# LEDDriverBoardV1_2.net
KiCad netlist of a schematic drawn in EAGLE
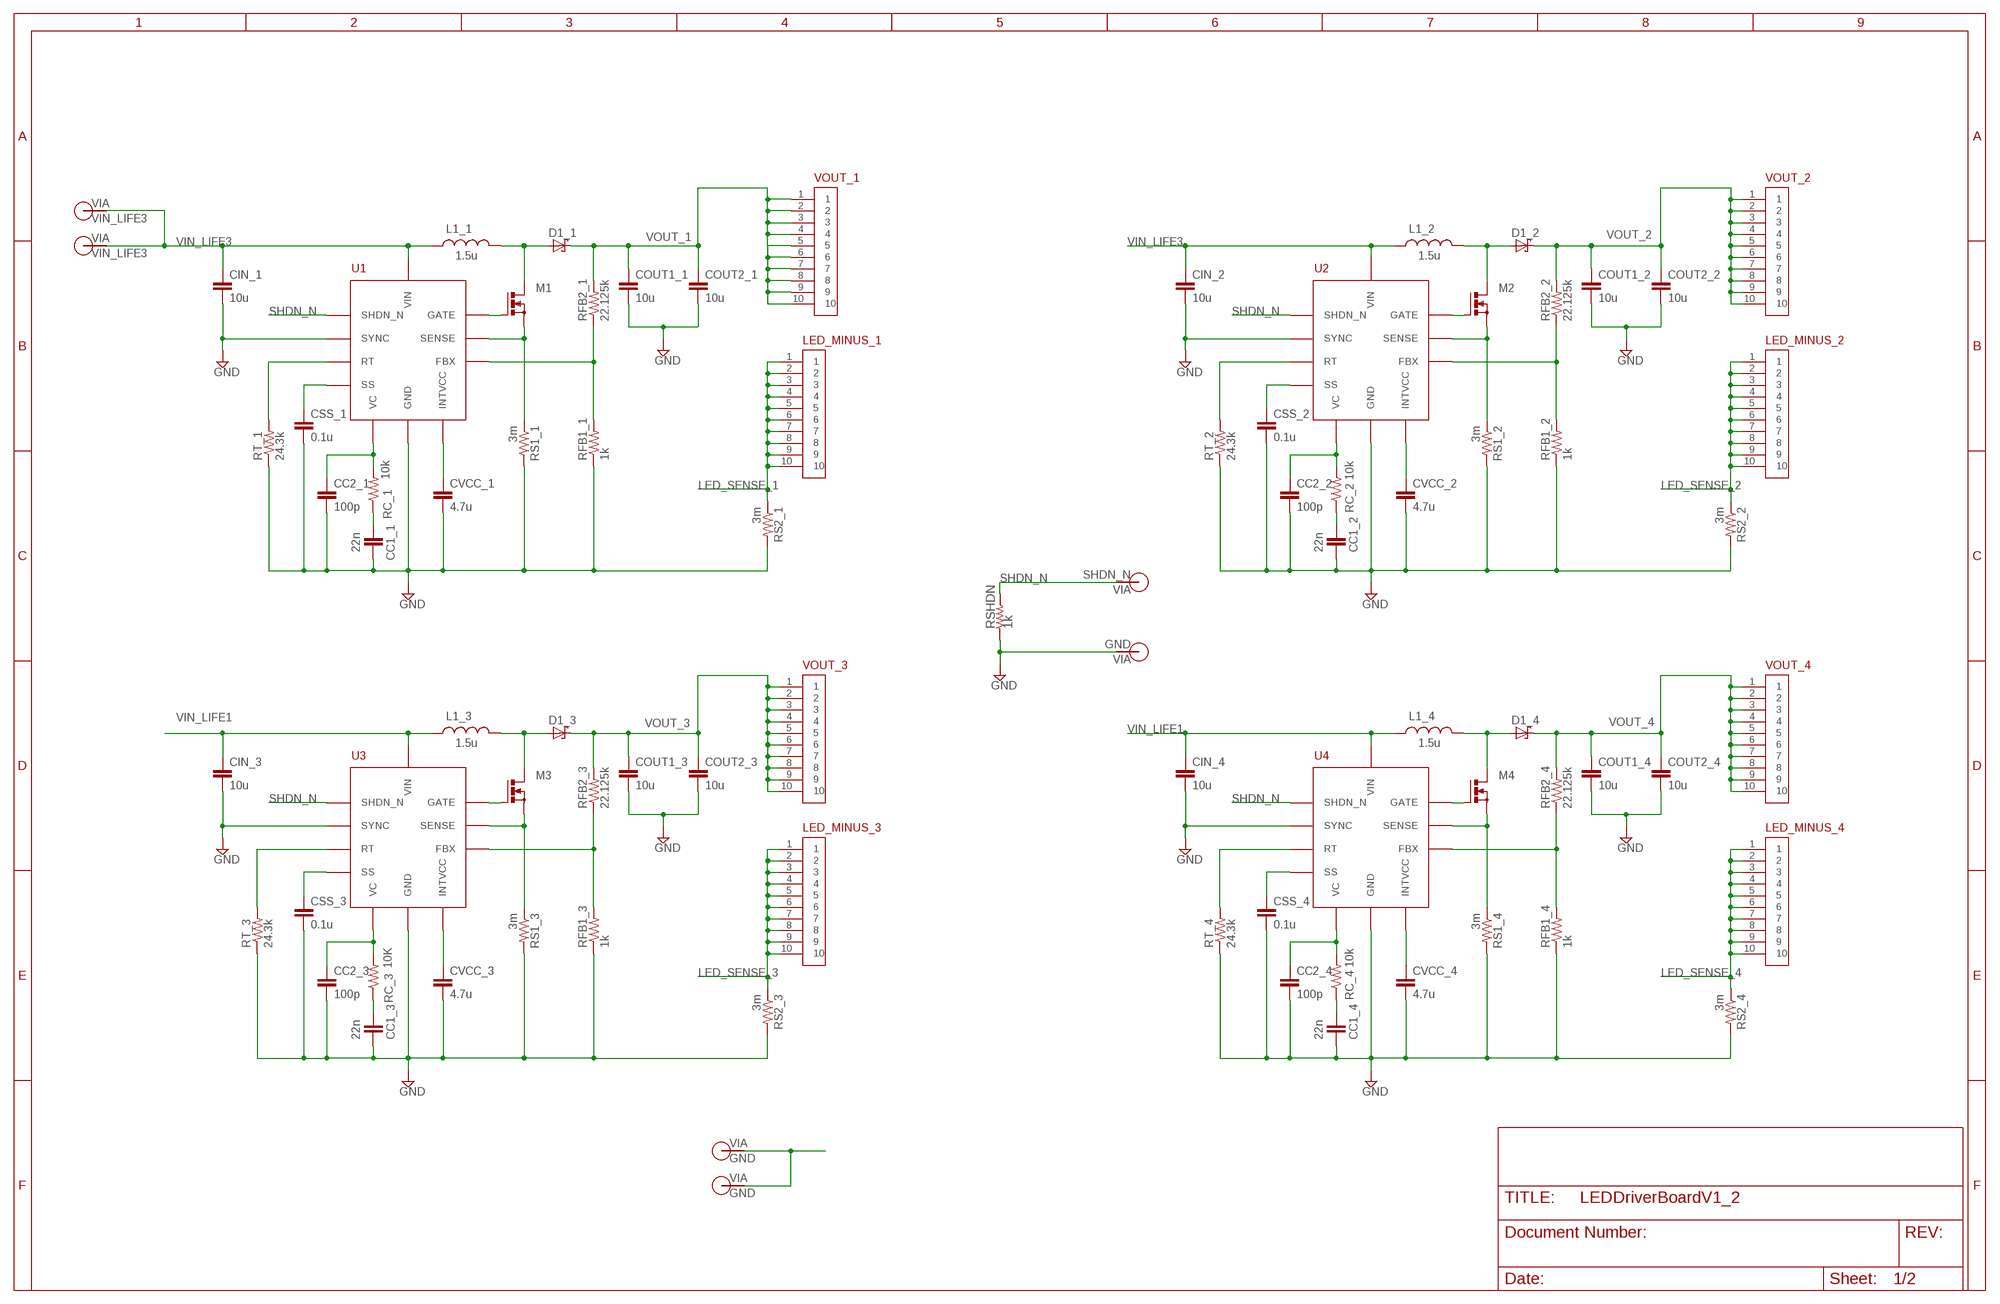
[diagram p0: schematic, sheet 1]
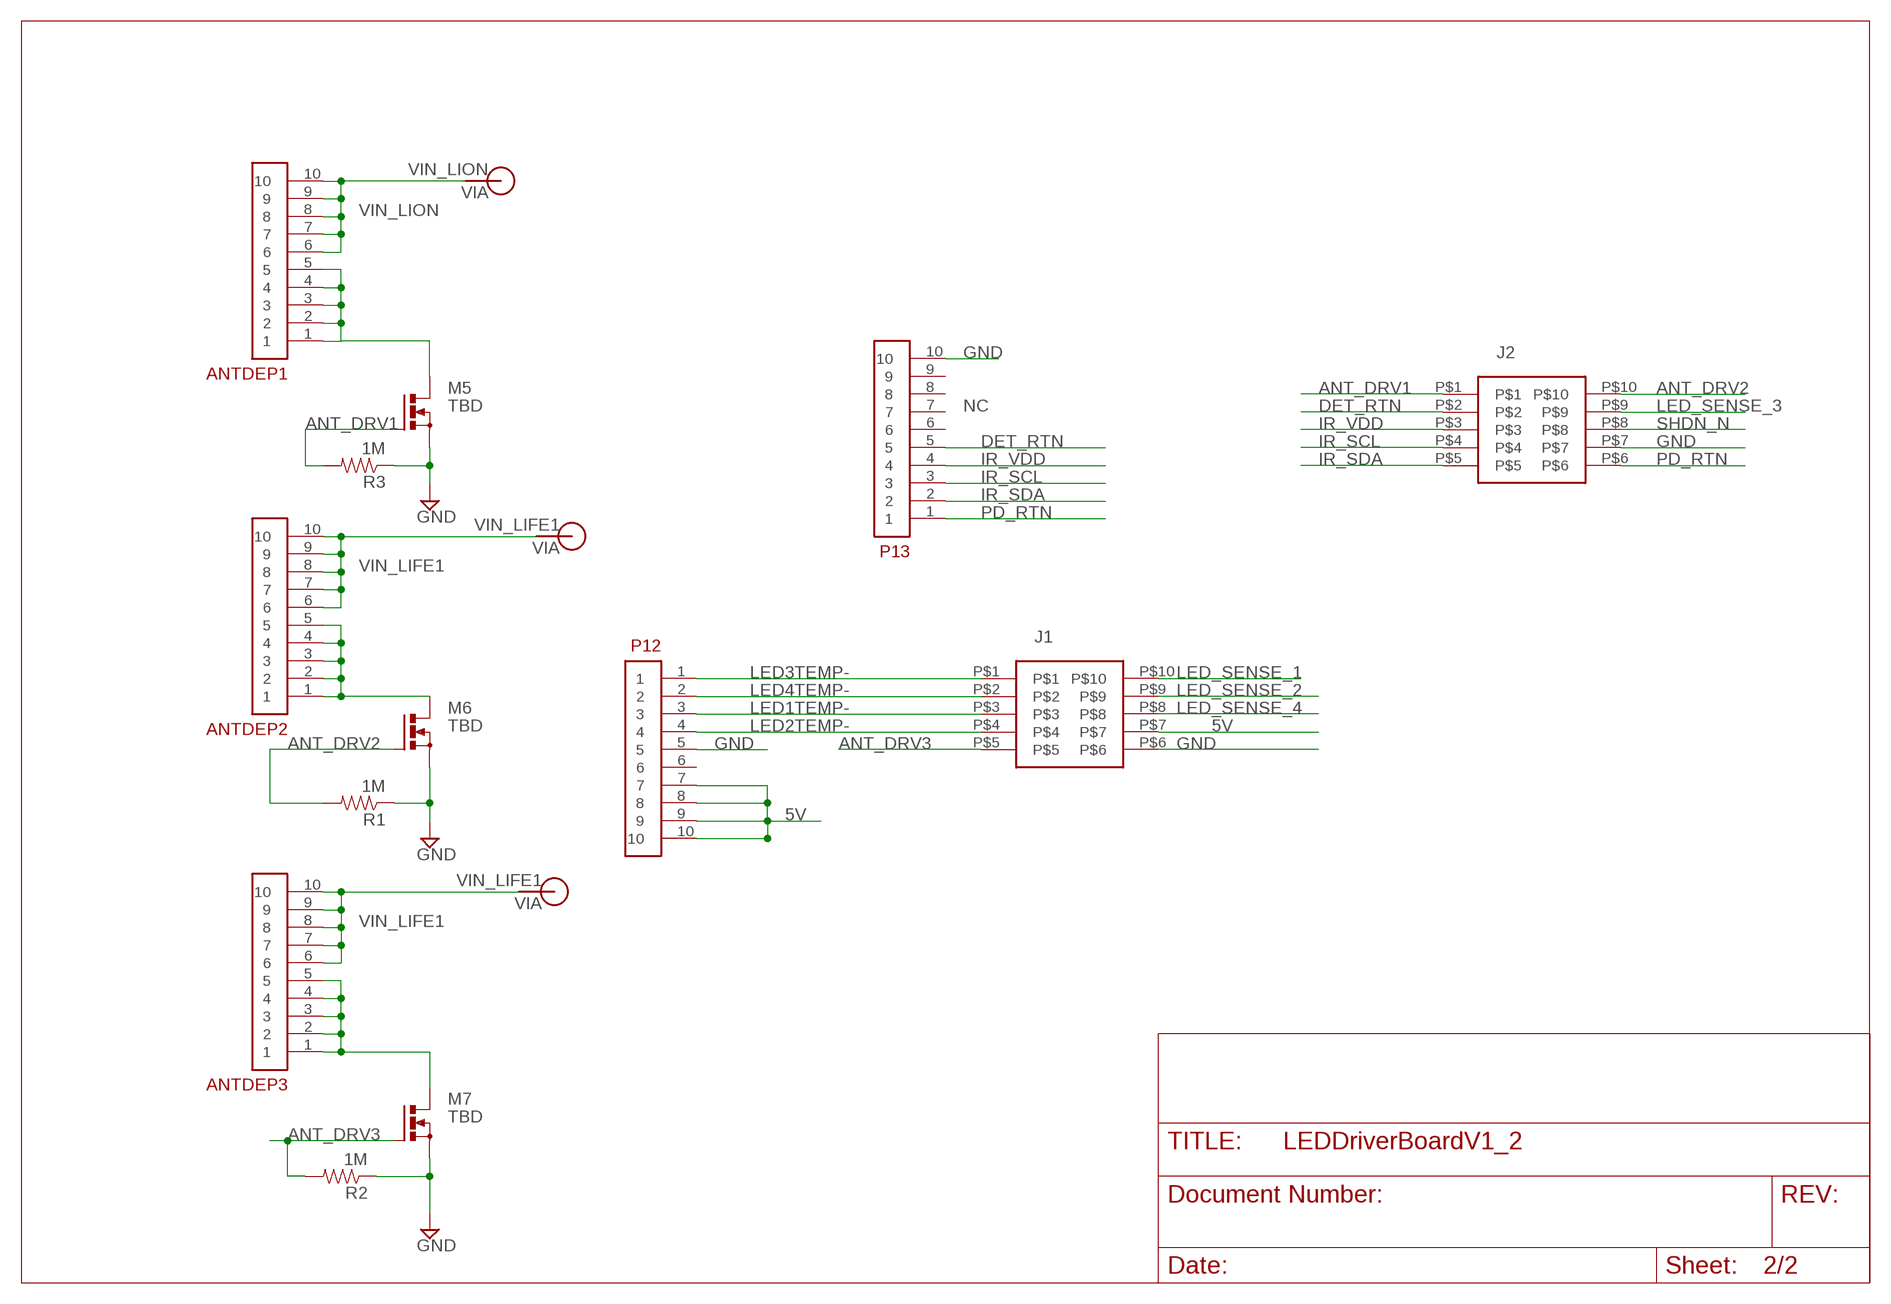
[diagram p1: schematic, sheet 2]

(export (version "E")
  (design (tool "Eeschema 10.0.6"))
  (components
    (comp (ref "CC1_1")
      (value "22n")
      (footprint "eagle-import:C0603")
      (libsource (lib "eagle-import") (part "C-EUC0603"))
    )
    (comp (ref "CC1_2")
      (value "22n")
      (footprint "eagle-import:C0603")
      (libsource (lib "eagle-import") (part "C-EUC0603"))
    )
    (comp (ref "CC1_3")
      (value "22n")
      (footprint "eagle-import:C0603")
      (libsource (lib "eagle-import") (part "C-EUC0603"))
    )
    (comp (ref "CC1_4")
      (value "22n")
      (footprint "eagle-import:C0603")
      (libsource (lib "eagle-import") (part "C-EUC0603"))
    )
    (comp (ref "CC2_1")
      (value "100p")
      (footprint "eagle-import:C0603")
      (libsource (lib "eagle-import") (part "C-EUC0603"))
    )
    (comp (ref "CC2_2")
      (value "100p")
      (footprint "eagle-import:C0603")
      (libsource (lib "eagle-import") (part "C-EUC0603"))
    )
    (comp (ref "CC2_3")
      (value "100p")
      (footprint "eagle-import:C0603")
      (libsource (lib "eagle-import") (part "C-EUC0603"))
    )
    (comp (ref "CC2_4")
      (value "100p")
      (footprint "eagle-import:C0603")
      (libsource (lib "eagle-import") (part "C-EUC0603"))
    )
    (comp (ref "CIN_1")
      (value "10u")
      (footprint "eagle-import:C1210")
      (libsource (lib "eagle-import") (part "C-EUC1210"))
    )
    (comp (ref "CIN_2")
      (value "10u")
      (footprint "eagle-import:C1210")
      (libsource (lib "eagle-import") (part "C-EUC1210"))
    )
    (comp (ref "CIN_3")
      (value "10u")
      (footprint "eagle-import:C1210")
      (libsource (lib "eagle-import") (part "C-EUC1210"))
    )
    (comp (ref "CIN_4")
      (value "10u")
      (footprint "eagle-import:C1210")
      (libsource (lib "eagle-import") (part "C-EUC1210"))
    )
    (comp (ref "COUT1_1")
      (value "10u")
      (footprint "eagle-import:C1210")
      (libsource (lib "eagle-import") (part "C-EUC1210"))
    )
    (comp (ref "COUT1_2")
      (value "10u")
      (footprint "eagle-import:C1210")
      (libsource (lib "eagle-import") (part "C-EUC1210"))
    )
    (comp (ref "COUT1_3")
      (value "10u")
      (footprint "eagle-import:C1210")
      (libsource (lib "eagle-import") (part "C-EUC1210"))
    )
    (comp (ref "COUT1_4")
      (value "10u")
      (footprint "eagle-import:C1210")
      (libsource (lib "eagle-import") (part "C-EUC1210"))
    )
    (comp (ref "COUT2_1")
      (value "10u")
      (footprint "eagle-import:C1210")
      (libsource (lib "eagle-import") (part "C-EUC1210"))
    )
    (comp (ref "COUT2_2")
      (value "10u")
      (footprint "eagle-import:C1210")
      (libsource (lib "eagle-import") (part "C-EUC1210"))
    )
    (comp (ref "COUT2_3")
      (value "10u")
      (footprint "eagle-import:C1210")
      (libsource (lib "eagle-import") (part "C-EUC1210"))
    )
    (comp (ref "COUT2_4")
      (value "10u")
      (footprint "eagle-import:C1210")
      (libsource (lib "eagle-import") (part "C-EUC1210"))
    )
    (comp (ref "CSS_1")
      (value "0.1u")
      (footprint "eagle-import:C0603")
      (libsource (lib "eagle-import") (part "C-EUC0603"))
    )
    (comp (ref "CSS_2")
      (value "0.1u")
      (footprint "eagle-import:C0603")
      (libsource (lib "eagle-import") (part "C-EUC0603"))
    )
    (comp (ref "CSS_3")
      (value "0.1u")
      (footprint "eagle-import:C0603")
      (libsource (lib "eagle-import") (part "C-EUC0603"))
    )
    (comp (ref "CSS_4")
      (value "0.1u")
      (footprint "eagle-import:C0603")
      (libsource (lib "eagle-import") (part "C-EUC0603"))
    )
    (comp (ref "CVCC_1")
      (value "4.7u")
      (footprint "eagle-import:C0603")
      (libsource (lib "eagle-import") (part "C-EUC0603"))
    )
    (comp (ref "CVCC_2")
      (value "4.7u")
      (footprint "eagle-import:C0603")
      (libsource (lib "eagle-import") (part "C-EUC0603"))
    )
    (comp (ref "CVCC_3")
      (value "4.7u")
      (footprint "eagle-import:C0603")
      (libsource (lib "eagle-import") (part "C-EUC0603"))
    )
    (comp (ref "CVCC_4")
      (value "4.7u")
      (footprint "eagle-import:C0603")
      (libsource (lib "eagle-import") (part "C-EUC0603"))
    )
    (comp (ref "D1_1")
      (value "CDBZ5T30100-HF")
      (footprint "eagle-import:SMC(Z5-T)")
      (libsource (lib "eagle-import") (part "CDBZ5T30100-HF"))
    )
    (comp (ref "D1_2")
      (value "CDBZ5T30100-HF")
      (footprint "eagle-import:SMC(Z5-T)")
      (libsource (lib "eagle-import") (part "CDBZ5T30100-HF"))
    )
    (comp (ref "D1_3")
      (value "CDBZ5T30100-HF")
      (footprint "eagle-import:SMC(Z5-T)")
      (libsource (lib "eagle-import") (part "CDBZ5T30100-HF"))
    )
    (comp (ref "D1_4")
      (value "CDBZ5T30100-HF")
      (footprint "eagle-import:SMC(Z5-T)")
      (libsource (lib "eagle-import") (part "CDBZ5T30100-HF"))
    )
    (comp (ref "L1_1")
      (value "1.5u")
      (footprint "eagle-import:SRP1245A")
      (libsource (lib "eagle-import") (part "SRP1245A-1R5M"))
    )
    (comp (ref "L1_2")
      (value "1.5u")
      (footprint "eagle-import:SRP1245A")
      (libsource (lib "eagle-import") (part "SRP1245A-1R5M"))
    )
    (comp (ref "L1_3")
      (value "1.5u")
      (footprint "eagle-import:SRP1245A")
      (libsource (lib "eagle-import") (part "SRP1245A-1R5M"))
    )
    (comp (ref "L1_4")
      (value "1.5u")
      (footprint "eagle-import:SRP1245A")
      (libsource (lib "eagle-import") (part "SRP1245A-1R5M"))
    )
    (comp (ref "LED_MINUS_1")
      (value "M50-3120545")
      (footprint "eagle-import:10PINFEMALE")
      (libsource (lib "eagle-import") (part "M50-3120545"))
    )
    (comp (ref "LED_MINUS_2")
      (value "M50-3120545")
      (footprint "eagle-import:10PINFEMALE")
      (libsource (lib "eagle-import") (part "M50-3120545"))
    )
    (comp (ref "LED_MINUS_3")
      (value "M50-3120545")
      (footprint "eagle-import:10PINFEMALE")
      (libsource (lib "eagle-import") (part "M50-3120545"))
    )
    (comp (ref "LED_MINUS_4")
      (value "M50-3120545")
      (footprint "eagle-import:10PINFEMALE")
      (libsource (lib "eagle-import") (part "M50-3120545"))
    )
    (comp (ref "M1")
      (value "STL110N10F7")
      (footprint "eagle-import:POWERFLAT")
      (libsource (lib "eagle-import") (part "STL110N10F7"))
    )
    (comp (ref "M2")
      (value "STL110N10F7")
      (footprint "eagle-import:POWERFLAT")
      (libsource (lib "eagle-import") (part "STL110N10F7"))
    )
    (comp (ref "M3")
      (value "STL110N10F7")
      (footprint "eagle-import:POWERFLAT")
      (libsource (lib "eagle-import") (part "STL110N10F7"))
    )
    (comp (ref "M4")
      (value "STL110N10F7")
      (footprint "eagle-import:POWERFLAT")
      (libsource (lib "eagle-import") (part "STL110N10F7"))
    )
    (comp (ref "RC_1")
      (value "10k")
      (footprint "eagle-import:R0603")
      (libsource (lib "eagle-import") (part "R-US_R0603"))
    )
    (comp (ref "RC_2")
      (value "10k")
      (footprint "eagle-import:R0603")
      (libsource (lib "eagle-import") (part "R-US_R0603"))
    )
    (comp (ref "RC_3")
      (value "10K")
      (footprint "eagle-import:R0603")
      (libsource (lib "eagle-import") (part "R-US_R0603"))
    )
    (comp (ref "RC_4")
      (value "10k")
      (footprint "eagle-import:R0603")
      (libsource (lib "eagle-import") (part "R-US_R0603"))
    )
    (comp (ref "RFB1_1")
      (value "1k")
      (footprint "eagle-import:R0603")
      (libsource (lib "eagle-import") (part "R-US_R0603"))
    )
    (comp (ref "RFB1_2")
      (value "1k")
      (footprint "eagle-import:R0603")
      (libsource (lib "eagle-import") (part "R-US_R0603"))
    )
    (comp (ref "RFB1_3")
      (value "1k")
      (footprint "eagle-import:R0603")
      (libsource (lib "eagle-import") (part "R-US_R0603"))
    )
    (comp (ref "RFB1_4")
      (value "1k")
      (footprint "eagle-import:R0603")
      (libsource (lib "eagle-import") (part "R-US_R0603"))
    )
    (comp (ref "RFB2_1")
      (value "22.125k")
      (footprint "eagle-import:R0603")
      (libsource (lib "eagle-import") (part "R-US_R0603"))
    )
    (comp (ref "RFB2_2")
      (value "22.125k")
      (footprint "eagle-import:R0603")
      (libsource (lib "eagle-import") (part "R-US_R0603"))
    )
    (comp (ref "RFB2_3")
      (value "22.125k")
      (footprint "eagle-import:R0603")
      (libsource (lib "eagle-import") (part "R-US_R0603"))
    )
    (comp (ref "RFB2_4")
      (value "22.125k")
      (footprint "eagle-import:R0603")
      (libsource (lib "eagle-import") (part "R-US_R0603"))
    )
    (comp (ref "RS1_1")
      (value "3m")
      (footprint "eagle-import:ERJMS4S")
      (libsource (lib "eagle-import") (part "ERJMS4S"))
    )
    (comp (ref "RS1_2")
      (value "3m")
      (footprint "eagle-import:ERJMS4S")
      (libsource (lib "eagle-import") (part "ERJMS4S"))
    )
    (comp (ref "RS1_3")
      (value "3m")
      (footprint "eagle-import:ERJMS4S")
      (libsource (lib "eagle-import") (part "ERJMS4S"))
    )
    (comp (ref "RS1_4")
      (value "3m")
      (footprint "eagle-import:ERJMS4S")
      (libsource (lib "eagle-import") (part "ERJMS4S"))
    )
    (comp (ref "RS2_1")
      (value "3m")
      (footprint "eagle-import:ERJMS4S")
      (libsource (lib "eagle-import") (part "ERJMS4S"))
    )
    (comp (ref "RS2_2")
      (value "3m")
      (footprint "eagle-import:ERJMS4S")
      (libsource (lib "eagle-import") (part "ERJMS4S"))
    )
    (comp (ref "RS2_3")
      (value "3m")
      (footprint "eagle-import:ERJMS4S")
      (libsource (lib "eagle-import") (part "ERJMS4S"))
    )
    (comp (ref "RS2_4")
      (value "3m")
      (footprint "eagle-import:ERJMS4S")
      (libsource (lib "eagle-import") (part "ERJMS4S"))
    )
    (comp (ref "RSHDN")
      (value "1k")
      (footprint "eagle-import:0805")
      (libsource (lib "eagle-import") (part "RES0805"))
    )
    (comp (ref "RT_1")
      (value "24.3k")
      (footprint "eagle-import:R0603")
      (libsource (lib "eagle-import") (part "R-US_R0603"))
    )
    (comp (ref "RT_2")
      (value "24.3k")
      (footprint "eagle-import:R0603")
      (libsource (lib "eagle-import") (part "R-US_R0603"))
    )
    (comp (ref "RT_3")
      (value "24.3k")
      (footprint "eagle-import:R0603")
      (libsource (lib "eagle-import") (part "R-US_R0603"))
    )
    (comp (ref "RT_4")
      (value "24.3k")
      (footprint "eagle-import:R0603")
      (libsource (lib "eagle-import") (part "R-US_R0603"))
    )
    (comp (ref "U1")
      (value "LT3757")
      (footprint "eagle-import:MSOP10")
      (libsource (lib "eagle-import") (part "LT3757"))
    )
    (comp (ref "U2")
      (value "LT3757")
      (footprint "eagle-import:MSOP10")
      (libsource (lib "eagle-import") (part "LT3757"))
    )
    (comp (ref "U3")
      (value "LT3757")
      (footprint "eagle-import:MSOP10")
      (libsource (lib "eagle-import") (part "LT3757"))
    )
    (comp (ref "U4")
      (value "LT3757")
      (footprint "eagle-import:MSOP10")
      (libsource (lib "eagle-import") (part "LT3757"))
    )
    (comp (ref "V1")
      (value "GND")
      (footprint "eagle-import:VIA-120MIL")
      (libsource (lib "eagle-import") (part "VIA-120MIL"))
    )
    (comp (ref "V5")
      (value "GND")
      (footprint "eagle-import:VIA-120MIL")
      (libsource (lib "eagle-import") (part "VIA-120MIL"))
    )
    (comp (ref "V6")
      (value "VIN_LIFE3")
      (footprint "eagle-import:VIA-120MIL")
      (libsource (lib "eagle-import") (part "VIA-120MIL"))
    )
    (comp (ref "V7")
      (value "VIN_LIFE3")
      (footprint "eagle-import:VIA-120MIL")
      (libsource (lib "eagle-import") (part "VIA-120MIL"))
    )
    (comp (ref "V8")
      (value "SHDN_N")
      (footprint "eagle-import:VIA-60MIL-SQ")
      (libsource (lib "eagle-import") (part "VIA60MIL-SQ"))
    )
    (comp (ref "V9")
      (value "GND")
      (footprint "eagle-import:VIA-60MIL-SQ")
      (libsource (lib "eagle-import") (part "VIA60MIL-SQ"))
    )
    (comp (ref "VOUT_1")
      (value "M50-3120545")
      (footprint "eagle-import:10PINFEMALE")
      (libsource (lib "eagle-import") (part "M50-3120545"))
    )
    (comp (ref "VOUT_2")
      (value "M50-3120545")
      (footprint "eagle-import:10PINFEMALE")
      (libsource (lib "eagle-import") (part "M50-3120545"))
    )
    (comp (ref "VOUT_3")
      (value "M50-3120545")
      (footprint "eagle-import:10PINFEMALE")
      (libsource (lib "eagle-import") (part "M50-3120545"))
    )
    (comp (ref "VOUT_4")
      (value "M50-3120545")
      (footprint "eagle-import:10PINFEMALE")
      (libsource (lib "eagle-import") (part "M50-3120545"))
    )
    (comp (ref "ANTDEP1")
      (value "M50-3120545")
      (footprint "eagle-import:10PINFEMALE")
      (libsource (lib "eagle-import") (part "M50-3120545"))
    )
    (comp (ref "ANTDEP2")
      (value "M50-3120545")
      (footprint "eagle-import:10PINFEMALE")
      (libsource (lib "eagle-import") (part "M50-3120545"))
    )
    (comp (ref "ANTDEP3")
      (value "M50-3120545")
      (footprint "eagle-import:10PINFEMALE")
      (libsource (lib "eagle-import") (part "M50-3120545"))
    )
    (comp (ref "J1")
      (value "M80-53210")
      (footprint "eagle-import:M80-53210")
      (libsource (lib "eagle-import") (part "M80-53210"))
    )
    (comp (ref "J2")
      (value "M80-53210")
      (footprint "eagle-import:M80-53210")
      (libsource (lib "eagle-import") (part "M80-53210"))
    )
    (comp (ref "M5")
      (value "TBD")
      (footprint "eagle-import:DFN3.3X3.3")
      (libsource (lib "eagle-import") (part "AON7292"))
    )
    (comp (ref "M6")
      (value "TBD")
      (footprint "eagle-import:DFN3.3X3.3")
      (libsource (lib "eagle-import") (part "AON7292"))
    )
    (comp (ref "M7")
      (value "TBD")
      (footprint "eagle-import:DFN3.3X3.3")
      (libsource (lib "eagle-import") (part "AON7292"))
    )
    (comp (ref "P12")
      (value "M50-3120545")
      (footprint "eagle-import:10PINFEMALE")
      (libsource (lib "eagle-import") (part "M50-3120545"))
    )
    (comp (ref "P13")
      (value "M50-3120545")
      (footprint "eagle-import:10PINFEMALE")
      (libsource (lib "eagle-import") (part "M50-3120545"))
    )
    (comp (ref "R1")
      (value "1M")
      (footprint "eagle-import:0805")
      (libsource (lib "eagle-import") (part "RESISTOR"))
    )
    (comp (ref "R2")
      (value "1M")
      (footprint "eagle-import:0805")
      (libsource (lib "eagle-import") (part "RESISTOR"))
    )
    (comp (ref "R3")
      (value "1M")
      (footprint "eagle-import:0805")
      (libsource (lib "eagle-import") (part "RESISTOR"))
    )
    (comp (ref "V2")
      (value "VIN_LIFE1")
      (footprint "eagle-import:VIA-120MIL")
      (libsource (lib "eagle-import") (part "VIA-120MIL"))
    )
    (comp (ref "V3")
      (value "VIN_LIFE1")
      (footprint "eagle-import:VIA-120MIL")
      (libsource (lib "eagle-import") (part "VIA-120MIL"))
    )
    (comp (ref "V4")
      (value "VIN_LION")
      (footprint "eagle-import:VIA-120MIL")
      (libsource (lib "eagle-import") (part "VIA-120MIL"))
    )
  )
  (nets
    (net (code "1") (name "5V") (class "Default")
      (node (ref "J1") (pin "P$7") (pinfunction "P$7_P$7") (pintype "bidirectional"))
      (node (ref "P12") (pin "10") (pinfunction "10_10") (pintype "bidirectional"))
      (node (ref "P12") (pin "7") (pinfunction "7_7") (pintype "bidirectional"))
      (node (ref "P12") (pin "8") (pinfunction "8_8") (pintype "bidirectional"))
      (node (ref "P12") (pin "9") (pinfunction "9_9") (pintype "bidirectional"))
    )
    (net (code "2") (name "ANT_DRV1") (class "Default")
      (node (ref "J2") (pin "P$1") (pinfunction "P$1_P$1") (pintype "bidirectional"))
      (node (ref "M5") (pin "G") (pinfunction "G_G") (pintype "passive"))
      (node (ref "R3") (pin "2") (pinfunction "2_2") (pintype "passive"))
    )
    (net (code "3") (name "ANT_DRV2") (class "Default")
      (node (ref "J2") (pin "P$10") (pinfunction "P$10_P$10") (pintype "bidirectional"))
      (node (ref "M6") (pin "G") (pinfunction "G_G") (pintype "passive"))
      (node (ref "R1") (pin "2") (pinfunction "2_2") (pintype "passive"))
    )
    (net (code "4") (name "ANT_DRV3") (class "Default")
      (node (ref "J1") (pin "P$5") (pinfunction "P$5_P$5") (pintype "bidirectional"))
      (node (ref "M7") (pin "G") (pinfunction "G_G") (pintype "passive"))
      (node (ref "R2") (pin "2") (pinfunction "2_2") (pintype "passive"))
    )
    (net (code "5") (name "DET_RTN") (class "Default")
      (node (ref "J2") (pin "P$2") (pinfunction "P$2_P$2") (pintype "bidirectional"))
      (node (ref "P13") (pin "5") (pinfunction "5_5") (pintype "bidirectional"))
    )
    (net (code "6") (name "GND") (class "Default")
      (node (ref "CC1_1") (pin "2") (pinfunction "2_2") (pintype "passive"))
      (node (ref "CC1_2") (pin "2") (pinfunction "2_2") (pintype "passive"))
      (node (ref "CC1_3") (pin "2") (pinfunction "2_2") (pintype "passive"))
      (node (ref "CC1_4") (pin "2") (pinfunction "2_2") (pintype "passive"))
      (node (ref "CC2_1") (pin "2") (pinfunction "2_2") (pintype "passive"))
      (node (ref "CC2_2") (pin "2") (pinfunction "2_2") (pintype "passive"))
      (node (ref "CC2_3") (pin "2") (pinfunction "2_2") (pintype "passive"))
      (node (ref "CC2_4") (pin "2") (pinfunction "2_2") (pintype "passive"))
      (node (ref "CIN_1") (pin "2") (pinfunction "2_2") (pintype "passive"))
      (node (ref "CIN_2") (pin "2") (pinfunction "2_2") (pintype "passive"))
      (node (ref "CIN_3") (pin "2") (pinfunction "2_2") (pintype "passive"))
      (node (ref "CIN_4") (pin "2") (pinfunction "2_2") (pintype "passive"))
      (node (ref "COUT1_1") (pin "2") (pinfunction "2_2") (pintype "passive"))
      (node (ref "COUT1_2") (pin "2") (pinfunction "2_2") (pintype "passive"))
      (node (ref "COUT1_3") (pin "2") (pinfunction "2_2") (pintype "passive"))
      (node (ref "COUT1_4") (pin "2") (pinfunction "2_2") (pintype "passive"))
      (node (ref "COUT2_1") (pin "2") (pinfunction "2_2") (pintype "passive"))
      (node (ref "COUT2_2") (pin "2") (pinfunction "2_2") (pintype "passive"))
      (node (ref "COUT2_3") (pin "2") (pinfunction "2_2") (pintype "passive"))
      (node (ref "COUT2_4") (pin "2") (pinfunction "2_2") (pintype "passive"))
      (node (ref "CSS_1") (pin "2") (pinfunction "2_2") (pintype "passive"))
      (node (ref "CSS_2") (pin "2") (pinfunction "2_2") (pintype "passive"))
      (node (ref "CSS_3") (pin "2") (pinfunction "2_2") (pintype "passive"))
      (node (ref "CSS_4") (pin "2") (pinfunction "2_2") (pintype "passive"))
      (node (ref "CVCC_1") (pin "2") (pinfunction "2_2") (pintype "passive"))
      (node (ref "CVCC_2") (pin "2") (pinfunction "2_2") (pintype "passive"))
      (node (ref "CVCC_3") (pin "2") (pinfunction "2_2") (pintype "passive"))
      (node (ref "CVCC_4") (pin "2") (pinfunction "2_2") (pintype "passive"))
      (node (ref "J1") (pin "P$6") (pinfunction "P$6_P$6") (pintype "bidirectional"))
      (node (ref "J2") (pin "P$7") (pinfunction "P$7_P$7") (pintype "bidirectional"))
      (node (ref "M5") (pin "S1") (pinfunction "S_S1") (pintype "passive"))
      (node (ref "M5") (pin "S2") (pinfunction "S_S2") (pintype "passive"))
      (node (ref "M5") (pin "S3") (pinfunction "S_S3") (pintype "passive"))
      (node (ref "M6") (pin "S1") (pinfunction "S_S1") (pintype "passive"))
      (node (ref "M6") (pin "S2") (pinfunction "S_S2") (pintype "passive"))
      (node (ref "M6") (pin "S3") (pinfunction "S_S3") (pintype "passive"))
      (node (ref "M7") (pin "S1") (pinfunction "S_S1") (pintype "passive"))
      (node (ref "M7") (pin "S2") (pinfunction "S_S2") (pintype "passive"))
      (node (ref "M7") (pin "S3") (pinfunction "S_S3") (pintype "passive"))
      (node (ref "P12") (pin "5") (pinfunction "5_5") (pintype "bidirectional"))
      (node (ref "P13") (pin "10") (pinfunction "10_10") (pintype "bidirectional"))
      (node (ref "R1") (pin "1") (pinfunction "1_1") (pintype "passive"))
      (node (ref "R2") (pin "1") (pinfunction "1_1") (pintype "passive"))
      (node (ref "R3") (pin "1") (pinfunction "1_1") (pintype "passive"))
      (node (ref "RFB1_1") (pin "1") (pinfunction "1_1") (pintype "passive"))
      (node (ref "RFB1_2") (pin "1") (pinfunction "1_1") (pintype "passive"))
      (node (ref "RFB1_3") (pin "1") (pinfunction "1_1") (pintype "passive"))
      (node (ref "RFB1_4") (pin "1") (pinfunction "1_1") (pintype "passive"))
      (node (ref "RS1_1") (pin "B") (pinfunction "2_B") (pintype "passive"))
      (node (ref "RS1_2") (pin "B") (pinfunction "2_B") (pintype "passive"))
      (node (ref "RS1_3") (pin "B") (pinfunction "2_B") (pintype "passive"))
      (node (ref "RS1_4") (pin "B") (pinfunction "2_B") (pintype "passive"))
      (node (ref "RS2_1") (pin "B") (pinfunction "2_B") (pintype "passive"))
      (node (ref "RS2_2") (pin "B") (pinfunction "2_B") (pintype "passive"))
      (node (ref "RS2_3") (pin "B") (pinfunction "2_B") (pintype "passive"))
      (node (ref "RS2_4") (pin "B") (pinfunction "2_B") (pintype "passive"))
      (node (ref "RSHDN") (pin "1") (pinfunction "1_1") (pintype "passive"))
      (node (ref "RT_1") (pin "1") (pinfunction "1_1") (pintype "passive"))
      (node (ref "RT_2") (pin "1") (pinfunction "1_1") (pintype "passive"))
      (node (ref "RT_3") (pin "1") (pinfunction "1_1") (pintype "passive"))
      (node (ref "RT_4") (pin "1") (pinfunction "1_1") (pintype "passive"))
      (node (ref "U1") (pin "P$11") (pinfunction "GND_P$11") (pintype "bidirectional"))
      (node (ref "U1") (pin "P$5") (pinfunction "SYNC_P$5") (pintype "bidirectional"))
      (node (ref "U2") (pin "P$11") (pinfunction "GND_P$11") (pintype "bidirectional"))
      (node (ref "U2") (pin "P$5") (pinfunction "SYNC_P$5") (pintype "bidirectional"))
      (node (ref "U3") (pin "P$11") (pinfunction "GND_P$11") (pintype "bidirectional"))
      (node (ref "U3") (pin "P$5") (pinfunction "SYNC_P$5") (pintype "bidirectional"))
      (node (ref "U4") (pin "P$11") (pinfunction "GND_P$11") (pintype "bidirectional"))
      (node (ref "U4") (pin "P$5") (pinfunction "SYNC_P$5") (pintype "bidirectional"))
      (node (ref "V1") (pin "P$1") (pinfunction "P$1_P$1") (pintype "bidirectional"))
      (node (ref "V5") (pin "P$1") (pinfunction "P$1_P$1") (pintype "bidirectional"))
      (node (ref "V9") (pin "P$1") (pinfunction "P$1_P$1") (pintype "bidirectional"))
    )
    (net (code "7") (name "IR_SCL") (class "Default")
      (node (ref "J2") (pin "P$4") (pinfunction "P$4_P$4") (pintype "bidirectional"))
      (node (ref "P13") (pin "3") (pinfunction "3_3") (pintype "bidirectional"))
    )
    (net (code "8") (name "IR_SDA") (class "Default")
      (node (ref "J2") (pin "P$5") (pinfunction "P$5_P$5") (pintype "bidirectional"))
      (node (ref "P13") (pin "2") (pinfunction "2_2") (pintype "bidirectional"))
    )
    (net (code "9") (name "IR_VDD") (class "Default")
      (node (ref "J2") (pin "P$3") (pinfunction "P$3_P$3") (pintype "bidirectional"))
      (node (ref "P13") (pin "4") (pinfunction "4_4") (pintype "bidirectional"))
    )
    (net (code "10") (name "LED1TEMP-") (class "Default")
      (node (ref "J1") (pin "P$3") (pinfunction "P$3_P$3") (pintype "bidirectional"))
      (node (ref "P12") (pin "3") (pinfunction "3_3") (pintype "bidirectional"))
    )
    (net (code "11") (name "LED2TEMP-") (class "Default")
      (node (ref "J1") (pin "P$4") (pinfunction "P$4_P$4") (pintype "bidirectional"))
      (node (ref "P12") (pin "4") (pinfunction "4_4") (pintype "bidirectional"))
    )
    (net (code "12") (name "LED3TEMP-") (class "Default")
      (node (ref "J1") (pin "P$1") (pinfunction "P$1_P$1") (pintype "bidirectional"))
      (node (ref "P12") (pin "1") (pinfunction "1_1") (pintype "bidirectional"))
    )
    (net (code "13") (name "LED4TEMP-") (class "Default")
      (node (ref "J1") (pin "P$2") (pinfunction "P$2_P$2") (pintype "bidirectional"))
      (node (ref "P12") (pin "2") (pinfunction "2_2") (pintype "bidirectional"))
    )
    (net (code "14") (name "LED_SENSE_1") (class "Default")
      (node (ref "J1") (pin "P$10") (pinfunction "P$10_P$10") (pintype "bidirectional"))
      (node (ref "LED_MINUS_1") (pin "1") (pinfunction "1_1") (pintype "bidirectional"))
      (node (ref "LED_MINUS_1") (pin "10") (pinfunction "10_10") (pintype "bidirectional"))
      (node (ref "LED_MINUS_1") (pin "2") (pinfunction "2_2") (pintype "bidirectional"))
      (node (ref "LED_MINUS_1") (pin "3") (pinfunction "3_3") (pintype "bidirectional"))
      (node (ref "LED_MINUS_1") (pin "4") (pinfunction "4_4") (pintype "bidirectional"))
      (node (ref "LED_MINUS_1") (pin "5") (pinfunction "5_5") (pintype "bidirectional"))
      (node (ref "LED_MINUS_1") (pin "6") (pinfunction "6_6") (pintype "bidirectional"))
      (node (ref "LED_MINUS_1") (pin "7") (pinfunction "7_7") (pintype "bidirectional"))
      (node (ref "LED_MINUS_1") (pin "8") (pinfunction "8_8") (pintype "bidirectional"))
      (node (ref "LED_MINUS_1") (pin "9") (pinfunction "9_9") (pintype "bidirectional"))
      (node (ref "RS2_1") (pin "A") (pinfunction "1_A") (pintype "passive"))
    )
    (net (code "15") (name "LED_SENSE_2") (class "Default")
      (node (ref "J1") (pin "P$9") (pinfunction "P$9_P$9") (pintype "bidirectional"))
      (node (ref "LED_MINUS_2") (pin "1") (pinfunction "1_1") (pintype "bidirectional"))
      (node (ref "LED_MINUS_2") (pin "10") (pinfunction "10_10") (pintype "bidirectional"))
      (node (ref "LED_MINUS_2") (pin "2") (pinfunction "2_2") (pintype "bidirectional"))
      (node (ref "LED_MINUS_2") (pin "3") (pinfunction "3_3") (pintype "bidirectional"))
      (node (ref "LED_MINUS_2") (pin "4") (pinfunction "4_4") (pintype "bidirectional"))
      (node (ref "LED_MINUS_2") (pin "5") (pinfunction "5_5") (pintype "bidirectional"))
      (node (ref "LED_MINUS_2") (pin "6") (pinfunction "6_6") (pintype "bidirectional"))
      (node (ref "LED_MINUS_2") (pin "7") (pinfunction "7_7") (pintype "bidirectional"))
      (node (ref "LED_MINUS_2") (pin "8") (pinfunction "8_8") (pintype "bidirectional"))
      (node (ref "LED_MINUS_2") (pin "9") (pinfunction "9_9") (pintype "bidirectional"))
      (node (ref "RS2_2") (pin "A") (pinfunction "1_A") (pintype "passive"))
    )
    (net (code "16") (name "LED_SENSE_3") (class "Default")
      (node (ref "J2") (pin "P$9") (pinfunction "P$9_P$9") (pintype "bidirectional"))
      (node (ref "LED_MINUS_3") (pin "1") (pinfunction "1_1") (pintype "bidirectional"))
      (node (ref "LED_MINUS_3") (pin "10") (pinfunction "10_10") (pintype "bidirectional"))
      (node (ref "LED_MINUS_3") (pin "2") (pinfunction "2_2") (pintype "bidirectional"))
      (node (ref "LED_MINUS_3") (pin "3") (pinfunction "3_3") (pintype "bidirectional"))
      (node (ref "LED_MINUS_3") (pin "4") (pinfunction "4_4") (pintype "bidirectional"))
      (node (ref "LED_MINUS_3") (pin "5") (pinfunction "5_5") (pintype "bidirectional"))
      (node (ref "LED_MINUS_3") (pin "6") (pinfunction "6_6") (pintype "bidirectional"))
      (node (ref "LED_MINUS_3") (pin "7") (pinfunction "7_7") (pintype "bidirectional"))
      (node (ref "LED_MINUS_3") (pin "8") (pinfunction "8_8") (pintype "bidirectional"))
      (node (ref "LED_MINUS_3") (pin "9") (pinfunction "9_9") (pintype "bidirectional"))
      (node (ref "RS2_3") (pin "A") (pinfunction "1_A") (pintype "passive"))
    )
    (net (code "17") (name "LED_SENSE_4") (class "Default")
      (node (ref "J1") (pin "P$8") (pinfunction "P$8_P$8") (pintype "bidirectional"))
      (node (ref "LED_MINUS_4") (pin "1") (pinfunction "1_1") (pintype "bidirectional"))
      (node (ref "LED_MINUS_4") (pin "10") (pinfunction "10_10") (pintype "bidirectional"))
      (node (ref "LED_MINUS_4") (pin "2") (pinfunction "2_2") (pintype "bidirectional"))
      (node (ref "LED_MINUS_4") (pin "3") (pinfunction "3_3") (pintype "bidirectional"))
      (node (ref "LED_MINUS_4") (pin "4") (pinfunction "4_4") (pintype "bidirectional"))
      (node (ref "LED_MINUS_4") (pin "5") (pinfunction "5_5") (pintype "bidirectional"))
      (node (ref "LED_MINUS_4") (pin "6") (pinfunction "6_6") (pintype "bidirectional"))
      (node (ref "LED_MINUS_4") (pin "7") (pinfunction "7_7") (pintype "bidirectional"))
      (node (ref "LED_MINUS_4") (pin "8") (pinfunction "8_8") (pintype "bidirectional"))
      (node (ref "LED_MINUS_4") (pin "9") (pinfunction "9_9") (pintype "bidirectional"))
      (node (ref "RS2_4") (pin "A") (pinfunction "1_A") (pintype "passive"))
    )
    (net (code "18") (name "Net-(ANTDEP1-Pad1)") (class "Default")
      (node (ref "ANTDEP1") (pin "1") (pinfunction "1_1") (pintype "bidirectional"))
      (node (ref "ANTDEP1") (pin "2") (pinfunction "2_2") (pintype "bidirectional"))
      (node (ref "ANTDEP1") (pin "3") (pinfunction "3_3") (pintype "bidirectional"))
      (node (ref "ANTDEP1") (pin "4") (pinfunction "4_4") (pintype "bidirectional"))
      (node (ref "ANTDEP1") (pin "5") (pinfunction "5_5") (pintype "bidirectional"))
      (node (ref "M5") (pin "D1") (pinfunction "D_D1") (pintype "passive"))
      (node (ref "M5") (pin "D2") (pinfunction "D_D2") (pintype "passive"))
      (node (ref "M5") (pin "D3") (pinfunction "D_D3") (pintype "passive"))
      (node (ref "M5") (pin "D4") (pinfunction "D_D4") (pintype "passive"))
      (node (ref "M5") (pin "D5") (pinfunction "D_D5") (pintype "passive"))
    )
    (net (code "19") (name "Net-(ANTDEP2-Pad1)") (class "Default")
      (node (ref "ANTDEP2") (pin "1") (pinfunction "1_1") (pintype "bidirectional"))
      (node (ref "ANTDEP2") (pin "2") (pinfunction "2_2") (pintype "bidirectional"))
      (node (ref "ANTDEP2") (pin "3") (pinfunction "3_3") (pintype "bidirectional"))
      (node (ref "ANTDEP2") (pin "4") (pinfunction "4_4") (pintype "bidirectional"))
      (node (ref "ANTDEP2") (pin "5") (pinfunction "5_5") (pintype "bidirectional"))
      (node (ref "M6") (pin "D1") (pinfunction "D_D1") (pintype "passive"))
      (node (ref "M6") (pin "D2") (pinfunction "D_D2") (pintype "passive"))
      (node (ref "M6") (pin "D3") (pinfunction "D_D3") (pintype "passive"))
      (node (ref "M6") (pin "D4") (pinfunction "D_D4") (pintype "passive"))
      (node (ref "M6") (pin "D5") (pinfunction "D_D5") (pintype "passive"))
    )
    (net (code "20") (name "Net-(ANTDEP3-Pad1)") (class "Default")
      (node (ref "ANTDEP3") (pin "1") (pinfunction "1_1") (pintype "bidirectional"))
      (node (ref "ANTDEP3") (pin "2") (pinfunction "2_2") (pintype "bidirectional"))
      (node (ref "ANTDEP3") (pin "3") (pinfunction "3_3") (pintype "bidirectional"))
      (node (ref "ANTDEP3") (pin "4") (pinfunction "4_4") (pintype "bidirectional"))
      (node (ref "ANTDEP3") (pin "5") (pinfunction "5_5") (pintype "bidirectional"))
      (node (ref "M7") (pin "D1") (pinfunction "D_D1") (pintype "passive"))
      (node (ref "M7") (pin "D2") (pinfunction "D_D2") (pintype "passive"))
      (node (ref "M7") (pin "D3") (pinfunction "D_D3") (pintype "passive"))
      (node (ref "M7") (pin "D4") (pinfunction "D_D4") (pintype "passive"))
      (node (ref "M7") (pin "D5") (pinfunction "D_D5") (pintype "passive"))
    )
    (net (code "21") (name "Net-(CC1_1-Pad1)") (class "Default")
      (node (ref "CC1_1") (pin "1") (pinfunction "1_1") (pintype "passive"))
      (node (ref "RC_1") (pin "1") (pinfunction "1_1") (pintype "passive"))
    )
    (net (code "22") (name "Net-(CC1_2-Pad1)") (class "Default")
      (node (ref "CC1_2") (pin "1") (pinfunction "1_1") (pintype "passive"))
      (node (ref "RC_2") (pin "1") (pinfunction "1_1") (pintype "passive"))
    )
    (net (code "23") (name "Net-(CC1_3-Pad1)") (class "Default")
      (node (ref "CC1_3") (pin "1") (pinfunction "1_1") (pintype "passive"))
      (node (ref "RC_3") (pin "1") (pinfunction "1_1") (pintype "passive"))
    )
    (net (code "24") (name "Net-(CC1_4-Pad1)") (class "Default")
      (node (ref "CC1_4") (pin "1") (pinfunction "1_1") (pintype "passive"))
      (node (ref "RC_4") (pin "1") (pinfunction "1_1") (pintype "passive"))
    )
    (net (code "25") (name "Net-(L1_1-2)") (class "Default")
      (node (ref "D1_1") (pin "ANODE") (pinfunction "ANODE_ANODE") (pintype "passive"))
      (node (ref "L1_1") (pin "P$2") (pinfunction "2_P$2") (pintype "passive"))
      (node (ref "M1") (pin "D") (pinfunction "D_D") (pintype "passive"))
      (node (ref "M1") (pin "D5") (pinfunction "D_D5") (pintype "passive"))
      (node (ref "M1") (pin "D6") (pinfunction "D_D6") (pintype "passive"))
      (node (ref "M1") (pin "D7") (pinfunction "D_D7") (pintype "passive"))
      (node (ref "M1") (pin "D8") (pinfunction "D_D8") (pintype "passive"))
    )
    (net (code "26") (name "Net-(L1_2-2)") (class "Default")
      (node (ref "D1_2") (pin "ANODE") (pinfunction "ANODE_ANODE") (pintype "passive"))
      (node (ref "L1_2") (pin "P$2") (pinfunction "2_P$2") (pintype "passive"))
      (node (ref "M2") (pin "D") (pinfunction "D_D") (pintype "passive"))
      (node (ref "M2") (pin "D5") (pinfunction "D_D5") (pintype "passive"))
      (node (ref "M2") (pin "D6") (pinfunction "D_D6") (pintype "passive"))
      (node (ref "M2") (pin "D7") (pinfunction "D_D7") (pintype "passive"))
      (node (ref "M2") (pin "D8") (pinfunction "D_D8") (pintype "passive"))
    )
    (net (code "27") (name "Net-(L1_3-2)") (class "Default")
      (node (ref "D1_3") (pin "ANODE") (pinfunction "ANODE_ANODE") (pintype "passive"))
      (node (ref "L1_3") (pin "P$2") (pinfunction "2_P$2") (pintype "passive"))
      (node (ref "M3") (pin "D") (pinfunction "D_D") (pintype "passive"))
      (node (ref "M3") (pin "D5") (pinfunction "D_D5") (pintype "passive"))
      (node (ref "M3") (pin "D6") (pinfunction "D_D6") (pintype "passive"))
      (node (ref "M3") (pin "D7") (pinfunction "D_D7") (pintype "passive"))
      (node (ref "M3") (pin "D8") (pinfunction "D_D8") (pintype "passive"))
    )
    (net (code "28") (name "Net-(L1_4-2)") (class "Default")
      (node (ref "D1_4") (pin "ANODE") (pinfunction "ANODE_ANODE") (pintype "passive"))
      (node (ref "L1_4") (pin "P$2") (pinfunction "2_P$2") (pintype "passive"))
      (node (ref "M4") (pin "D") (pinfunction "D_D") (pintype "passive"))
      (node (ref "M4") (pin "D5") (pinfunction "D_D5") (pintype "passive"))
      (node (ref "M4") (pin "D6") (pinfunction "D_D6") (pintype "passive"))
      (node (ref "M4") (pin "D7") (pinfunction "D_D7") (pintype "passive"))
      (node (ref "M4") (pin "D8") (pinfunction "D_D8") (pintype "passive"))
    )
    (net (code "29") (name "Net-(RS1_1-1)") (class "Default")
      (node (ref "M1") (pin "S1") (pinfunction "S_S1") (pintype "passive"))
      (node (ref "M1") (pin "S2") (pinfunction "S_S2") (pintype "passive"))
      (node (ref "M1") (pin "S3") (pinfunction "S_S3") (pintype "passive"))
      (node (ref "RS1_1") (pin "A") (pinfunction "1_A") (pintype "passive"))
      (node (ref "U1") (pin "P$6") (pinfunction "SENSE_P$6") (pintype "bidirectional"))
    )
    (net (code "30") (name "Net-(RS1_2-1)") (class "Default")
      (node (ref "M2") (pin "S1") (pinfunction "S_S1") (pintype "passive"))
      (node (ref "M2") (pin "S2") (pinfunction "S_S2") (pintype "passive"))
      (node (ref "M2") (pin "S3") (pinfunction "S_S3") (pintype "passive"))
      (node (ref "RS1_2") (pin "A") (pinfunction "1_A") (pintype "passive"))
      (node (ref "U2") (pin "P$6") (pinfunction "SENSE_P$6") (pintype "bidirectional"))
    )
    (net (code "31") (name "Net-(RS1_3-1)") (class "Default")
      (node (ref "M3") (pin "S1") (pinfunction "S_S1") (pintype "passive"))
      (node (ref "M3") (pin "S2") (pinfunction "S_S2") (pintype "passive"))
      (node (ref "M3") (pin "S3") (pinfunction "S_S3") (pintype "passive"))
      (node (ref "RS1_3") (pin "A") (pinfunction "1_A") (pintype "passive"))
      (node (ref "U3") (pin "P$6") (pinfunction "SENSE_P$6") (pintype "bidirectional"))
    )
    (net (code "32") (name "Net-(RS1_4-1)") (class "Default")
      (node (ref "M4") (pin "S1") (pinfunction "S_S1") (pintype "passive"))
      (node (ref "M4") (pin "S2") (pinfunction "S_S2") (pintype "passive"))
      (node (ref "M4") (pin "S3") (pinfunction "S_S3") (pintype "passive"))
      (node (ref "RS1_4") (pin "A") (pinfunction "1_A") (pintype "passive"))
      (node (ref "U4") (pin "P$6") (pinfunction "SENSE_P$6") (pintype "bidirectional"))
    )
    (net (code "33") (name "Net-(U1-FBX)") (class "Default")
      (node (ref "RFB1_1") (pin "2") (pinfunction "2_2") (pintype "passive"))
      (node (ref "RFB2_1") (pin "1") (pinfunction "1_1") (pintype "passive"))
      (node (ref "U1") (pin "P$2") (pinfunction "FBX_P$2") (pintype "bidirectional"))
    )
    (net (code "34") (name "Net-(U1-GATE)") (class "Default")
      (node (ref "M1") (pin "G") (pinfunction "G_G") (pintype "passive"))
      (node (ref "U1") (pin "P$7") (pinfunction "GATE_P$7") (pintype "bidirectional"))
    )
    (net (code "35") (name "Net-(U1-INTVCC)") (class "Default")
      (node (ref "CVCC_1") (pin "1") (pinfunction "1_1") (pintype "passive"))
      (node (ref "U1") (pin "P$8") (pinfunction "INTVCC_P$8") (pintype "bidirectional"))
    )
    (net (code "36") (name "Net-(U1-RT)") (class "Default")
      (node (ref "RT_1") (pin "2") (pinfunction "2_2") (pintype "passive"))
      (node (ref "U1") (pin "P$4") (pinfunction "RT_P$4") (pintype "bidirectional"))
    )
    (net (code "37") (name "Net-(U1-SS)") (class "Default")
      (node (ref "CSS_1") (pin "1") (pinfunction "1_1") (pintype "passive"))
      (node (ref "U1") (pin "P$3") (pinfunction "SS_P$3") (pintype "bidirectional"))
    )
    (net (code "38") (name "Net-(U1-VC)") (class "Default")
      (node (ref "CC2_1") (pin "1") (pinfunction "1_1") (pintype "passive"))
      (node (ref "RC_1") (pin "2") (pinfunction "2_2") (pintype "passive"))
      (node (ref "U1") (pin "P$1") (pinfunction "VC_P$1") (pintype "bidirectional"))
    )
    (net (code "39") (name "Net-(U2-FBX)") (class "Default")
      (node (ref "RFB1_2") (pin "2") (pinfunction "2_2") (pintype "passive"))
      (node (ref "RFB2_2") (pin "1") (pinfunction "1_1") (pintype "passive"))
      (node (ref "U2") (pin "P$2") (pinfunction "FBX_P$2") (pintype "bidirectional"))
    )
    (net (code "40") (name "Net-(U2-GATE)") (class "Default")
      (node (ref "M2") (pin "G") (pinfunction "G_G") (pintype "passive"))
      (node (ref "U2") (pin "P$7") (pinfunction "GATE_P$7") (pintype "bidirectional"))
    )
    (net (code "41") (name "Net-(U2-INTVCC)") (class "Default")
      (node (ref "CVCC_2") (pin "1") (pinfunction "1_1") (pintype "passive"))
      (node (ref "U2") (pin "P$8") (pinfunction "INTVCC_P$8") (pintype "bidirectional"))
    )
    (net (code "42") (name "Net-(U2-RT)") (class "Default")
      (node (ref "RT_2") (pin "2") (pinfunction "2_2") (pintype "passive"))
      (node (ref "U2") (pin "P$4") (pinfunction "RT_P$4") (pintype "bidirectional"))
    )
    (net (code "43") (name "Net-(U2-SS)") (class "Default")
      (node (ref "CSS_2") (pin "1") (pinfunction "1_1") (pintype "passive"))
      (node (ref "U2") (pin "P$3") (pinfunction "SS_P$3") (pintype "bidirectional"))
    )
    (net (code "44") (name "Net-(U2-VC)") (class "Default")
      (node (ref "CC2_2") (pin "1") (pinfunction "1_1") (pintype "passive"))
      (node (ref "RC_2") (pin "2") (pinfunction "2_2") (pintype "passive"))
      (node (ref "U2") (pin "P$1") (pinfunction "VC_P$1") (pintype "bidirectional"))
    )
    (net (code "45") (name "Net-(U3-FBX)") (class "Default")
      (node (ref "RFB1_3") (pin "2") (pinfunction "2_2") (pintype "passive"))
      (node (ref "RFB2_3") (pin "1") (pinfunction "1_1") (pintype "passive"))
      (node (ref "U3") (pin "P$2") (pinfunction "FBX_P$2") (pintype "bidirectional"))
    )
    (net (code "46") (name "Net-(U3-GATE)") (class "Default")
      (node (ref "M3") (pin "G") (pinfunction "G_G") (pintype "passive"))
      (node (ref "U3") (pin "P$7") (pinfunction "GATE_P$7") (pintype "bidirectional"))
    )
    (net (code "47") (name "Net-(U3-INTVCC)") (class "Default")
      (node (ref "CVCC_3") (pin "1") (pinfunction "1_1") (pintype "passive"))
      (node (ref "U3") (pin "P$8") (pinfunction "INTVCC_P$8") (pintype "bidirectional"))
    )
    (net (code "48") (name "Net-(U3-RT)") (class "Default")
      (node (ref "RT_3") (pin "2") (pinfunction "2_2") (pintype "passive"))
      (node (ref "U3") (pin "P$4") (pinfunction "RT_P$4") (pintype "bidirectional"))
    )
    (net (code "49") (name "Net-(U3-SS)") (class "Default")
      (node (ref "CSS_3") (pin "1") (pinfunction "1_1") (pintype "passive"))
      (node (ref "U3") (pin "P$3") (pinfunction "SS_P$3") (pintype "bidirectional"))
    )
    (net (code "50") (name "Net-(U3-VC)") (class "Default")
      (node (ref "CC2_3") (pin "1") (pinfunction "1_1") (pintype "passive"))
      (node (ref "RC_3") (pin "2") (pinfunction "2_2") (pintype "passive"))
      (node (ref "U3") (pin "P$1") (pinfunction "VC_P$1") (pintype "bidirectional"))
    )
    (net (code "51") (name "Net-(U4-FBX)") (class "Default")
      (node (ref "RFB1_4") (pin "2") (pinfunction "2_2") (pintype "passive"))
      (node (ref "RFB2_4") (pin "1") (pinfunction "1_1") (pintype "passive"))
      (node (ref "U4") (pin "P$2") (pinfunction "FBX_P$2") (pintype "bidirectional"))
    )
    (net (code "52") (name "Net-(U4-GATE)") (class "Default")
      (node (ref "M4") (pin "G") (pinfunction "G_G") (pintype "passive"))
      (node (ref "U4") (pin "P$7") (pinfunction "GATE_P$7") (pintype "bidirectional"))
    )
    (net (code "53") (name "Net-(U4-INTVCC)") (class "Default")
      (node (ref "CVCC_4") (pin "1") (pinfunction "1_1") (pintype "passive"))
      (node (ref "U4") (pin "P$8") (pinfunction "INTVCC_P$8") (pintype "bidirectional"))
    )
    (net (code "54") (name "Net-(U4-RT)") (class "Default")
      (node (ref "RT_4") (pin "2") (pinfunction "2_2") (pintype "passive"))
      (node (ref "U4") (pin "P$4") (pinfunction "RT_P$4") (pintype "bidirectional"))
    )
    (net (code "55") (name "Net-(U4-SS)") (class "Default")
      (node (ref "CSS_4") (pin "1") (pinfunction "1_1") (pintype "passive"))
      (node (ref "U4") (pin "P$3") (pinfunction "SS_P$3") (pintype "bidirectional"))
    )
    (net (code "56") (name "Net-(U4-VC)") (class "Default")
      (node (ref "CC2_4") (pin "1") (pinfunction "1_1") (pintype "passive"))
      (node (ref "RC_4") (pin "2") (pinfunction "2_2") (pintype "passive"))
      (node (ref "U4") (pin "P$1") (pinfunction "VC_P$1") (pintype "bidirectional"))
    )
    (net (code "57") (name "PD_RTN") (class "Default")
      (node (ref "J2") (pin "P$6") (pinfunction "P$6_P$6") (pintype "bidirectional"))
      (node (ref "P13") (pin "1") (pinfunction "1_1") (pintype "bidirectional"))
    )
    (net (code "58") (name "SHDN_N") (class "Default")
      (node (ref "J2") (pin "P$8") (pinfunction "P$8_P$8") (pintype "bidirectional"))
      (node (ref "RSHDN") (pin "2") (pinfunction "2_2") (pintype "passive"))
      (node (ref "U1") (pin "P$9") (pinfunction "SHDN_N_P$9") (pintype "bidirectional"))
      (node (ref "U2") (pin "P$9") (pinfunction "SHDN_N_P$9") (pintype "bidirectional"))
      (node (ref "U3") (pin "P$9") (pinfunction "SHDN_N_P$9") (pintype "bidirectional"))
      (node (ref "U4") (pin "P$9") (pinfunction "SHDN_N_P$9") (pintype "bidirectional"))
      (node (ref "V8") (pin "P$1") (pinfunction "P$1_P$1") (pintype "bidirectional"))
    )
    (net (code "59") (name "VIN_LIFE1") (class "Default")
      (node (ref "ANTDEP2") (pin "10") (pinfunction "10_10") (pintype "bidirectional"))
      (node (ref "ANTDEP2") (pin "6") (pinfunction "6_6") (pintype "bidirectional"))
      (node (ref "ANTDEP2") (pin "7") (pinfunction "7_7") (pintype "bidirectional"))
      (node (ref "ANTDEP2") (pin "8") (pinfunction "8_8") (pintype "bidirectional"))
      (node (ref "ANTDEP2") (pin "9") (pinfunction "9_9") (pintype "bidirectional"))
      (node (ref "ANTDEP3") (pin "10") (pinfunction "10_10") (pintype "bidirectional"))
      (node (ref "ANTDEP3") (pin "6") (pinfunction "6_6") (pintype "bidirectional"))
      (node (ref "ANTDEP3") (pin "7") (pinfunction "7_7") (pintype "bidirectional"))
      (node (ref "ANTDEP3") (pin "8") (pinfunction "8_8") (pintype "bidirectional"))
      (node (ref "ANTDEP3") (pin "9") (pinfunction "9_9") (pintype "bidirectional"))
      (node (ref "CIN_3") (pin "1") (pinfunction "1_1") (pintype "passive"))
      (node (ref "CIN_4") (pin "1") (pinfunction "1_1") (pintype "passive"))
      (node (ref "L1_3") (pin "P$1") (pinfunction "1_P$1") (pintype "passive"))
      (node (ref "L1_4") (pin "P$1") (pinfunction "1_P$1") (pintype "passive"))
      (node (ref "U3") (pin "P$10") (pinfunction "VIN_P$10") (pintype "bidirectional"))
      (node (ref "U4") (pin "P$10") (pinfunction "VIN_P$10") (pintype "bidirectional"))
      (node (ref "V2") (pin "P$1") (pinfunction "P$1_P$1") (pintype "bidirectional"))
      (node (ref "V3") (pin "P$1") (pinfunction "P$1_P$1") (pintype "bidirectional"))
    )
    (net (code "60") (name "VIN_LIFE3") (class "Default")
      (node (ref "CIN_1") (pin "1") (pinfunction "1_1") (pintype "passive"))
      (node (ref "CIN_2") (pin "1") (pinfunction "1_1") (pintype "passive"))
      (node (ref "L1_1") (pin "P$1") (pinfunction "1_P$1") (pintype "passive"))
      (node (ref "L1_2") (pin "P$1") (pinfunction "1_P$1") (pintype "passive"))
      (node (ref "U1") (pin "P$10") (pinfunction "VIN_P$10") (pintype "bidirectional"))
      (node (ref "U2") (pin "P$10") (pinfunction "VIN_P$10") (pintype "bidirectional"))
      (node (ref "V6") (pin "P$1") (pinfunction "P$1_P$1") (pintype "bidirectional"))
      (node (ref "V7") (pin "P$1") (pinfunction "P$1_P$1") (pintype "bidirectional"))
    )
    (net (code "61") (name "VIN_LION") (class "Default")
      (node (ref "ANTDEP1") (pin "10") (pinfunction "10_10") (pintype "bidirectional"))
      (node (ref "ANTDEP1") (pin "6") (pinfunction "6_6") (pintype "bidirectional"))
      (node (ref "ANTDEP1") (pin "7") (pinfunction "7_7") (pintype "bidirectional"))
      (node (ref "ANTDEP1") (pin "8") (pinfunction "8_8") (pintype "bidirectional"))
      (node (ref "ANTDEP1") (pin "9") (pinfunction "9_9") (pintype "bidirectional"))
      (node (ref "V4") (pin "P$1") (pinfunction "P$1_P$1") (pintype "bidirectional"))
    )
    (net (code "62") (name "VOUT_1") (class "Default")
      (node (ref "COUT1_1") (pin "1") (pinfunction "1_1") (pintype "passive"))
      (node (ref "COUT2_1") (pin "1") (pinfunction "1_1") (pintype "passive"))
      (node (ref "D1_1") (pin "CATHODE") (pinfunction "CATHODE_CATHODE") (pintype "passive"))
      (node (ref "RFB2_1") (pin "2") (pinfunction "2_2") (pintype "passive"))
      (node (ref "VOUT_1") (pin "1") (pinfunction "1_1") (pintype "bidirectional"))
      (node (ref "VOUT_1") (pin "10") (pinfunction "10_10") (pintype "bidirectional"))
      (node (ref "VOUT_1") (pin "2") (pinfunction "2_2") (pintype "bidirectional"))
      (node (ref "VOUT_1") (pin "3") (pinfunction "3_3") (pintype "bidirectional"))
      (node (ref "VOUT_1") (pin "4") (pinfunction "4_4") (pintype "bidirectional"))
      (node (ref "VOUT_1") (pin "5") (pinfunction "5_5") (pintype "bidirectional"))
      (node (ref "VOUT_1") (pin "6") (pinfunction "6_6") (pintype "bidirectional"))
      (node (ref "VOUT_1") (pin "7") (pinfunction "7_7") (pintype "bidirectional"))
      (node (ref "VOUT_1") (pin "8") (pinfunction "8_8") (pintype "bidirectional"))
      (node (ref "VOUT_1") (pin "9") (pinfunction "9_9") (pintype "bidirectional"))
    )
    (net (code "63") (name "VOUT_2") (class "Default")
      (node (ref "COUT1_2") (pin "1") (pinfunction "1_1") (pintype "passive"))
      (node (ref "COUT2_2") (pin "1") (pinfunction "1_1") (pintype "passive"))
      (node (ref "D1_2") (pin "CATHODE") (pinfunction "CATHODE_CATHODE") (pintype "passive"))
      (node (ref "RFB2_2") (pin "2") (pinfunction "2_2") (pintype "passive"))
      (node (ref "VOUT_2") (pin "1") (pinfunction "1_1") (pintype "bidirectional"))
      (node (ref "VOUT_2") (pin "10") (pinfunction "10_10") (pintype "bidirectional"))
      (node (ref "VOUT_2") (pin "2") (pinfunction "2_2") (pintype "bidirectional"))
      (node (ref "VOUT_2") (pin "3") (pinfunction "3_3") (pintype "bidirectional"))
      (node (ref "VOUT_2") (pin "4") (pinfunction "4_4") (pintype "bidirectional"))
      (node (ref "VOUT_2") (pin "5") (pinfunction "5_5") (pintype "bidirectional"))
      (node (ref "VOUT_2") (pin "6") (pinfunction "6_6") (pintype "bidirectional"))
      (node (ref "VOUT_2") (pin "7") (pinfunction "7_7") (pintype "bidirectional"))
      (node (ref "VOUT_2") (pin "8") (pinfunction "8_8") (pintype "bidirectional"))
      (node (ref "VOUT_2") (pin "9") (pinfunction "9_9") (pintype "bidirectional"))
    )
    (net (code "64") (name "VOUT_3") (class "Default")
      (node (ref "COUT1_3") (pin "1") (pinfunction "1_1") (pintype "passive"))
      (node (ref "COUT2_3") (pin "1") (pinfunction "1_1") (pintype "passive"))
      (node (ref "D1_3") (pin "CATHODE") (pinfunction "CATHODE_CATHODE") (pintype "passive"))
      (node (ref "RFB2_3") (pin "2") (pinfunction "2_2") (pintype "passive"))
      (node (ref "VOUT_3") (pin "1") (pinfunction "1_1") (pintype "bidirectional"))
      (node (ref "VOUT_3") (pin "10") (pinfunction "10_10") (pintype "bidirectional"))
      (node (ref "VOUT_3") (pin "2") (pinfunction "2_2") (pintype "bidirectional"))
      (node (ref "VOUT_3") (pin "3") (pinfunction "3_3") (pintype "bidirectional"))
      (node (ref "VOUT_3") (pin "4") (pinfunction "4_4") (pintype "bidirectional"))
      (node (ref "VOUT_3") (pin "5") (pinfunction "5_5") (pintype "bidirectional"))
      (node (ref "VOUT_3") (pin "6") (pinfunction "6_6") (pintype "bidirectional"))
      (node (ref "VOUT_3") (pin "7") (pinfunction "7_7") (pintype "bidirectional"))
      (node (ref "VOUT_3") (pin "8") (pinfunction "8_8") (pintype "bidirectional"))
      (node (ref "VOUT_3") (pin "9") (pinfunction "9_9") (pintype "bidirectional"))
    )
    (net (code "65") (name "VOUT_4") (class "Default")
      (node (ref "COUT1_4") (pin "1") (pinfunction "1_1") (pintype "passive"))
      (node (ref "COUT2_4") (pin "1") (pinfunction "1_1") (pintype "passive"))
      (node (ref "D1_4") (pin "CATHODE") (pinfunction "CATHODE_CATHODE") (pintype "passive"))
      (node (ref "RFB2_4") (pin "2") (pinfunction "2_2") (pintype "passive"))
      (node (ref "VOUT_4") (pin "1") (pinfunction "1_1") (pintype "bidirectional"))
      (node (ref "VOUT_4") (pin "10") (pinfunction "10_10") (pintype "bidirectional"))
      (node (ref "VOUT_4") (pin "2") (pinfunction "2_2") (pintype "bidirectional"))
      (node (ref "VOUT_4") (pin "3") (pinfunction "3_3") (pintype "bidirectional"))
      (node (ref "VOUT_4") (pin "4") (pinfunction "4_4") (pintype "bidirectional"))
      (node (ref "VOUT_4") (pin "5") (pinfunction "5_5") (pintype "bidirectional"))
      (node (ref "VOUT_4") (pin "6") (pinfunction "6_6") (pintype "bidirectional"))
      (node (ref "VOUT_4") (pin "7") (pinfunction "7_7") (pintype "bidirectional"))
      (node (ref "VOUT_4") (pin "8") (pinfunction "8_8") (pintype "bidirectional"))
      (node (ref "VOUT_4") (pin "9") (pinfunction "9_9") (pintype "bidirectional"))
    )
    (net (code "66") (name "unconnected-(P12-Pad6)") (class "Default")
      (node (ref "P12") (pin "6") (pinfunction "6_6") (pintype "bidirectional"))
    )
    (net (code "67") (name "unconnected-(P13-Pad6)") (class "Default")
      (node (ref "P13") (pin "6") (pinfunction "6_6") (pintype "bidirectional"))
    )
    (net (code "68") (name "unconnected-(P13-Pad7)") (class "Default")
      (node (ref "P13") (pin "7") (pinfunction "7_7") (pintype "bidirectional"))
    )
    (net (code "69") (name "unconnected-(P13-Pad8)") (class "Default")
      (node (ref "P13") (pin "8") (pinfunction "8_8") (pintype "bidirectional"))
    )
    (net (code "70") (name "unconnected-(P13-Pad9)") (class "Default")
      (node (ref "P13") (pin "9") (pinfunction "9_9") (pintype "bidirectional"))
    )
  )
)
